# 06_Communication.net
KiCad netlist of a schematic drawn in Altium Designer
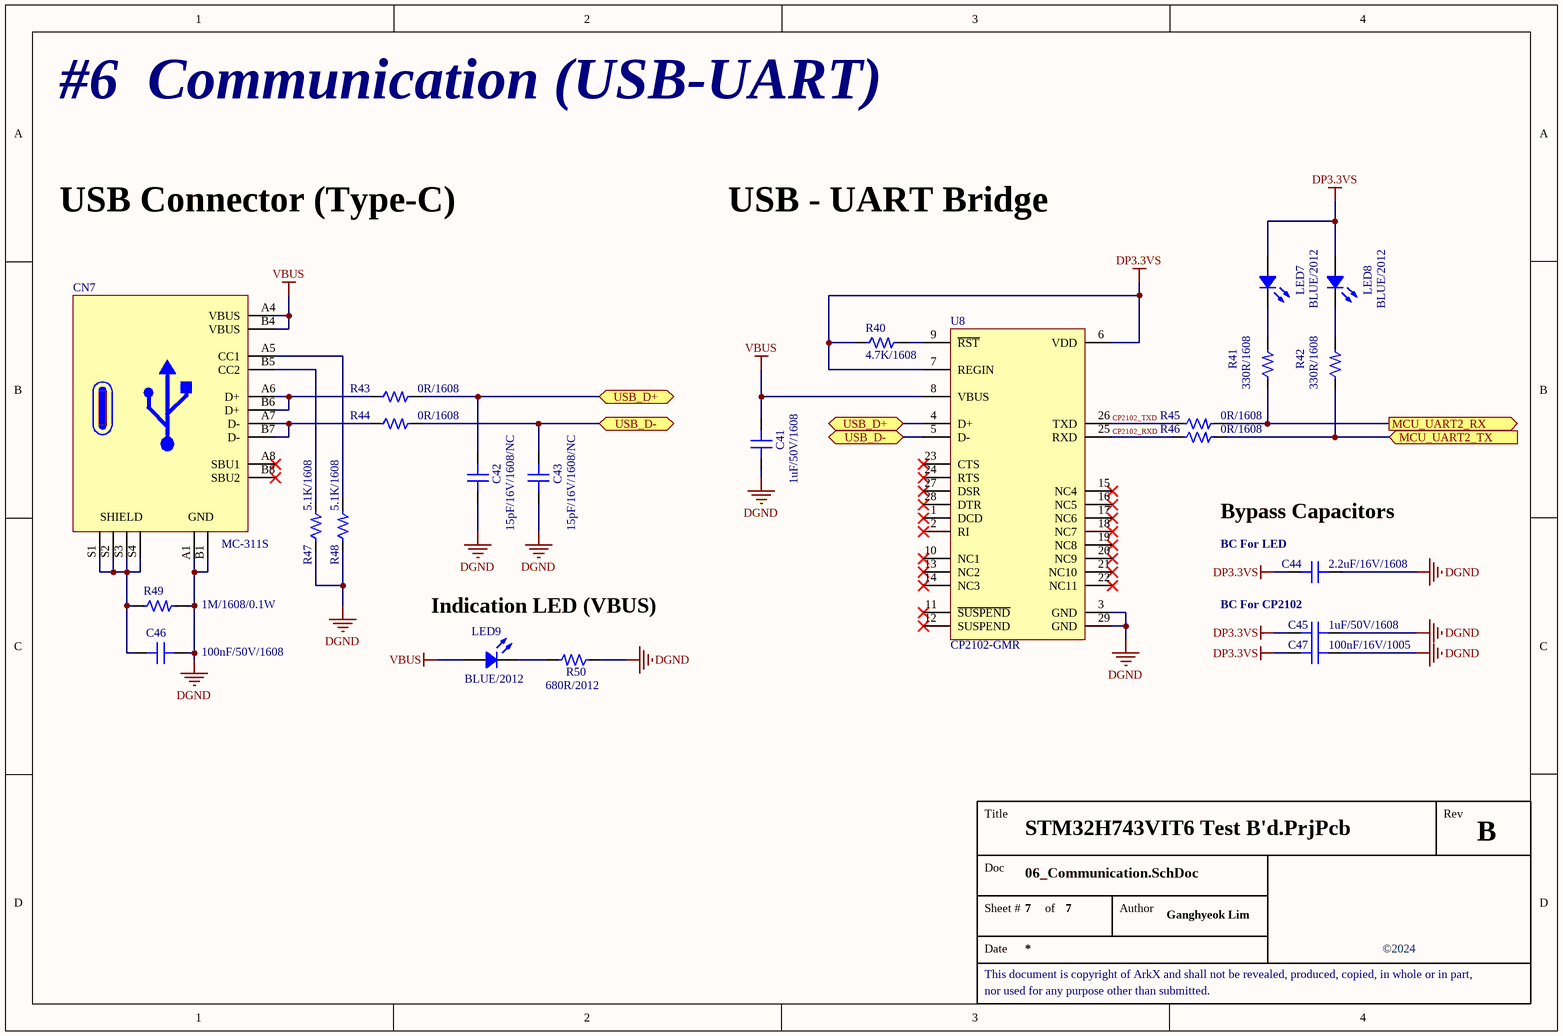
[diagram p0: 06_Communication.SchDoc]

(export (version "E")
  (design (tool "Eeschema 10.0.6"))
  (components
    (comp (ref "C41")
      (value "1uF/50V/1608")
      (footprint "CAP 1608 (0603_INCH)")
      (description "Ceramic CAP_1uF/50V/1608")
      (fields (field (name "LCSC PART #") "C15849"))
      (libsource (lib "Arkx") (part "CAP_1uF/50V/1608"))
    )
    (comp (ref "C42")
      (value "15pF/16V/1608/NC")
      (footprint "CAP 1608 (0603_INCH)/NC")
      (description "Ceramic CAP_15pF/16V/1608")
      (libsource (lib "Arkx") (part "CAP_NC_15pF/16V/1608"))
    )
    (comp (ref "C43")
      (value "15pF/16V/1608/NC")
      (footprint "CAP 1608 (0603_INCH)/NC")
      (description "Ceramic CAP_15pF/16V/1608")
      (libsource (lib "Arkx") (part "CAP_NC_15pF/16V/1608"))
    )
    (comp (ref "C44")
      (value "2.2uF/16V/1608")
      (footprint "CAP 1608 (0603_INCH)")
      (description "Ceramic CAP_2.2uF/16V/1608")
      (fields (field (name "LCSC PART #") "C23630"))
      (libsource (lib "Arkx") (part "CAP_2.2uF/16V/1608"))
    )
    (comp (ref "C45")
      (value "1uF/50V/1608")
      (footprint "CAP 1608 (0603_INCH)")
      (description "Ceramic CAP_1uF/50V/1608")
      (fields (field (name "LCSC PART #") "C15849"))
      (libsource (lib "Arkx") (part "CAP_1uF/50V/1608"))
    )
    (comp (ref "C46")
      (value "100nF/50V/1608")
      (footprint "CAP 1608 (0603_INCH)")
      (description "Ceramic CAP_100nF/50V/1608")
      (fields (field (name "LCSC PART #") "C14663"))
      (libsource (lib "Arkx") (part "CAP_100nF/50V/1608"))
    )
    (comp (ref "C47")
      (value "100nF/16V/1005")
      (footprint "CAP 1005 (0402_INCH)")
      (description "Ceramic CAP_100nF/16V/1005")
      (fields (field (name "LCSC PART #") "C1525"))
      (libsource (lib "Arkx") (part "CAP_100nF/16V/1005"))
    )
    (comp (ref "CN7")
      (value "MC-311S")
      (footprint "CON USB-Type-C (16P)")
      (description "USB 2.0 5A 1 Surface Mount 16 Female -35℃~+75℃ Type-C SMD  USB Connectors ROHS")
      (fields (field (name "LCSC PART #") "C2977718"))
      (libsource (lib "Arkx") (part "CON_USB-Type-C"))
    )
    (comp (ref "LED7")
      (value "BLUE/2012")
      (footprint "LED MHT170RGBCT (BLUE)")
      (fields (field (name "LCSC PART #") "C2962094"))
      (libsource (lib "Arkx") (part "LED_MHT170RGBCT(BLUE)"))
    )
    (comp (ref "LED8")
      (value "BLUE/2012")
      (footprint "LED MHT170RGBCT (BLUE)")
      (fields (field (name "LCSC PART #") "C2962094"))
      (libsource (lib "Arkx") (part "LED_MHT170RGBCT(BLUE)"))
    )
    (comp (ref "LED9")
      (value "BLUE/2012")
      (footprint "LED MHT170RGBCT (BLUE)")
      (fields (field (name "LCSC PART #") "C2962094"))
      (libsource (lib "Arkx") (part "LED_MHT170RGBCT(BLUE)"))
    )
    (comp (ref "R40")
      (value "4.7K/1608")
      (footprint "RES 1608 (0603_inch)")
      (description "RES_4.7K/1608/0.1W")
      (fields (field (name "LCSC PART #") "C23162"))
      (libsource (lib "Arkx") (part "RES_4.7K/1608/0.1W"))
    )
    (comp (ref "R41")
      (value "330R/1608")
      (footprint "RES 1608 (0603_inch)")
      (description "RES_330R/1608/0.1W")
      (fields (field (name "LCSC PART #") "C23138"))
      (libsource (lib "Arkx") (part "RES_330R/1608/0.1W"))
    )
    (comp (ref "R42")
      (value "330R/1608")
      (footprint "RES 1608 (0603_inch)")
      (description "RES_330R/1608/0.1W")
      (fields (field (name "LCSC PART #") "C23138"))
      (libsource (lib "Arkx") (part "RES_330R/1608/0.1W"))
    )
    (comp (ref "R43")
      (value "0R/1608")
      (footprint "RES 1608 (0603_inch)")
      (description "RES_0R/1608/0.1W")
      (fields (field (name "LCSC PART #") "C21189"))
      (libsource (lib "Arkx") (part "RES_0R/1608/0.1W"))
    )
    (comp (ref "R44")
      (value "0R/1608")
      (footprint "RES 1608 (0603_inch)")
      (description "RES_0R/1608/0.1W")
      (fields (field (name "LCSC PART #") "C21189"))
      (libsource (lib "Arkx") (part "RES_0R/1608/0.1W"))
    )
    (comp (ref "R45")
      (value "0R/1608")
      (footprint "RES 1608 (0603_inch)")
      (description "RES_0R/1608/0.1W")
      (fields (field (name "LCSC PART #") "C21189"))
      (libsource (lib "Arkx") (part "RES_0R/1608/0.1W"))
    )
    (comp (ref "R46")
      (value "0R/1608")
      (footprint "RES 1608 (0603_inch)")
      (description "RES_0R/1608/0.1W")
      (fields (field (name "LCSC PART #") "C21189"))
      (libsource (lib "Arkx") (part "RES_0R/1608/0.1W"))
    )
    (comp (ref "R47")
      (value "5.1K/1608")
      (footprint "RES 1608 (0603_inch)")
      (description "RES_5.1K/1608/0.1W")
      (fields (field (name "LCSC PART #") "C23186"))
      (libsource (lib "Arkx") (part "RES_5.1K/1608/0.1W"))
    )
    (comp (ref "R48")
      (value "5.1K/1608")
      (footprint "RES 1608 (0603_inch)")
      (description "RES_5.1K/1608/0.1W")
      (fields (field (name "LCSC PART #") "C23186"))
      (libsource (lib "Arkx") (part "RES_5.1K/1608/0.1W"))
    )
    (comp (ref "R49")
      (value "1M/1608/0.1W")
      (footprint "RES 1608 (0603_inch)")
      (description "RES_1M/1608/0.1W")
      (fields (field (name "LCSC PART #") "C22935"))
      (libsource (lib "Arkx") (part "RES_1M/1608/0.1W"))
    )
    (comp (ref "R50")
      (value "680R/2012")
      (footprint "RES 2012 (0805_inch)")
      (description "RES_680R/2012/0.125W")
      (fields (field (name "LCSC PART #") "C17798"))
      (libsource (lib "Arkx") (part "RES_680R/2012/0.125W"))
    )
    (comp (ref "U8")
      (value "CP2102-GMR")
      (footprint "QFN-28 (5x5mm)")
      (description "Transceiver 1Mbps USB 1/1 QFN-28_5x5x05P  USB ICs ROHS")
      (fields (field (name "LCSC PART #") "C6568"))
      (libsource (lib "Arkx") (part "IC_USB_CP2102"))
    )
  )
  (nets
    (net (code "1") (name "/CP2102_RXD") (class "Default")
      (node (ref "R46") (pin "1") (pinfunction "1_1") (pintype "passive"))
      (node (ref "U8") (pin "25") (pinfunction "RXD_25") (pintype "passive"))
    )
    (net (code "2") (name "/CP2102_TXD") (class "Default")
      (node (ref "R45") (pin "1") (pinfunction "1_1") (pintype "passive"))
      (node (ref "U8") (pin "26") (pinfunction "TXD_26") (pintype "passive"))
    )
    (net (code "3") (name "/MCU_UART2_RX") (class "Default")
      (node (ref "R41") (pin "1") (pinfunction "1_1") (pintype "passive"))
      (node (ref "R45") (pin "2") (pinfunction "2_2") (pintype "passive"))
    )
    (net (code "4") (name "/MCU_UART2_TX") (class "Default")
      (node (ref "R42") (pin "1") (pinfunction "1_1") (pintype "passive"))
      (node (ref "R46") (pin "2") (pinfunction "2_2") (pintype "passive"))
    )
    (net (code "5") (name "/USB_D+") (class "Default")
      (node (ref "C42") (pin "2") (pinfunction "2_2") (pintype "passive"))
      (node (ref "R43") (pin "2") (pinfunction "2_2") (pintype "passive"))
      (node (ref "U8") (pin "4") (pinfunction "D+_4") (pintype "passive"))
    )
    (net (code "6") (name "/USB_D-") (class "Default")
      (node (ref "C43") (pin "2") (pinfunction "2_2") (pintype "passive"))
      (node (ref "R44") (pin "2") (pinfunction "2_2") (pintype "passive"))
      (node (ref "U8") (pin "5") (pinfunction "D-_5") (pintype "passive"))
    )
    (net (code "7") (name "DGND") (class "Default")
      (node (ref "C41") (pin "1") (pinfunction "1_1") (pintype "passive"))
      (node (ref "C42") (pin "1") (pinfunction "1_1") (pintype "passive"))
      (node (ref "C43") (pin "1") (pinfunction "1_1") (pintype "passive"))
      (node (ref "C44") (pin "2") (pinfunction "2_2") (pintype "passive"))
      (node (ref "C45") (pin "1") (pinfunction "1_1") (pintype "passive"))
      (node (ref "C46") (pin "2") (pinfunction "2_2") (pintype "passive"))
      (node (ref "C47") (pin "1") (pinfunction "1_1") (pintype "passive"))
      (node (ref "CN7") (pin "A1") (pinfunction "GND_A1") (pintype "passive"))
      (node (ref "CN7") (pin "B1") (pinfunction "GND_B1") (pintype "passive"))
      (node (ref "R47") (pin "1") (pinfunction "1_1") (pintype "passive"))
      (node (ref "R48") (pin "1") (pinfunction "1_1") (pintype "passive"))
      (node (ref "R49") (pin "2") (pinfunction "2_2") (pintype "passive"))
      (node (ref "R50") (pin "1") (pinfunction "1_1") (pintype "passive"))
      (node (ref "U8") (pin "29") (pinfunction "GND_29") (pintype "passive"))
      (node (ref "U8") (pin "3") (pinfunction "GND_3") (pintype "passive"))
    )
    (net (code "8") (name "DP3.3VS") (class "Default")
      (node (ref "C44") (pin "1") (pinfunction "1_1") (pintype "passive"))
      (node (ref "C45") (pin "2") (pinfunction "2_2") (pintype "passive"))
      (node (ref "C47") (pin "2") (pinfunction "2_2") (pintype "passive"))
      (node (ref "LED7") (pin "4") (pinfunction "Common_Anode_4") (pintype "passive"))
      (node (ref "LED8") (pin "4") (pinfunction "Common_Anode_4") (pintype "passive"))
      (node (ref "R40") (pin "1") (pinfunction "1_1") (pintype "passive"))
      (node (ref "U8") (pin "6") (pinfunction "VDD_6") (pintype "passive"))
      (node (ref "U8") (pin "7") (pinfunction "REGIN_7") (pintype "passive"))
    )
    (net (code "9") (name "Net-(C46-Pad1)") (class "Default")
      (node (ref "C46") (pin "1") (pinfunction "1_1") (pintype "passive"))
      (node (ref "CN7") (pin "S1") (pinfunction "SHIELD_S1") (pintype "passive"))
      (node (ref "CN7") (pin "S2") (pinfunction "SHIELD_S2") (pintype "passive"))
      (node (ref "CN7") (pin "S3") (pinfunction "SHIELD_S3") (pintype "passive"))
      (node (ref "CN7") (pin "S4") (pinfunction "SHIELD_S4") (pintype "passive"))
      (node (ref "R49") (pin "1") (pinfunction "1_1") (pintype "passive"))
    )
    (net (code "10") (name "Net-(CN7-CC1)") (class "Default")
      (node (ref "CN7") (pin "A5") (pinfunction "CC1_A5") (pintype "passive"))
      (node (ref "R48") (pin "2") (pinfunction "2_2") (pintype "passive"))
    )
    (net (code "11") (name "Net-(CN7-CC2)") (class "Default")
      (node (ref "CN7") (pin "B5") (pinfunction "CC2_B5") (pintype "passive"))
      (node (ref "R47") (pin "2") (pinfunction "2_2") (pintype "passive"))
    )
    (net (code "12") (name "Net-(CN7-D+-PadA6)") (class "Default")
      (node (ref "CN7") (pin "A6") (pinfunction "D+_A6") (pintype "passive"))
      (node (ref "CN7") (pin "B6") (pinfunction "D+_B6") (pintype "passive"))
      (node (ref "R43") (pin "1") (pinfunction "1_1") (pintype "passive"))
    )
    (net (code "13") (name "Net-(CN7-D--PadA7)") (class "Default")
      (node (ref "CN7") (pin "A7") (pinfunction "D-_A7") (pintype "passive"))
      (node (ref "CN7") (pin "B7") (pinfunction "D-_B7") (pintype "passive"))
      (node (ref "R44") (pin "1") (pinfunction "1_1") (pintype "passive"))
    )
    (net (code "14") (name "Net-(LED7-BLUE)") (class "Default")
      (node (ref "LED7") (pin "3") (pinfunction "BLUE_3") (pintype "passive"))
      (node (ref "R41") (pin "2") (pinfunction "2_2") (pintype "passive"))
    )
    (net (code "15") (name "Net-(LED8-BLUE)") (class "Default")
      (node (ref "LED8") (pin "3") (pinfunction "BLUE_3") (pintype "passive"))
      (node (ref "R42") (pin "2") (pinfunction "2_2") (pintype "passive"))
    )
    (net (code "16") (name "Net-(LED9-BLUE)") (class "Default")
      (node (ref "LED9") (pin "3") (pinfunction "BLUE_3") (pintype "passive"))
      (node (ref "R50") (pin "2") (pinfunction "2_2") (pintype "passive"))
    )
    (net (code "17") (name "Net-(U8-~{RST})") (class "Default")
      (node (ref "R40") (pin "2") (pinfunction "2_2") (pintype "passive"))
      (node (ref "U8") (pin "9") (pinfunction "~{RST}_9") (pintype "passive"))
    )
    (net (code "18") (name "VBUS") (class "Default")
      (node (ref "C41") (pin "2") (pinfunction "2_2") (pintype "passive"))
      (node (ref "CN7") (pin "A4") (pinfunction "VBUS_A4") (pintype "passive"))
      (node (ref "CN7") (pin "B4") (pinfunction "VBUS_B4") (pintype "passive"))
      (node (ref "LED9") (pin "4") (pinfunction "Common_Anode_4") (pintype "passive"))
      (node (ref "U8") (pin "8") (pinfunction "VBUS_8") (pintype "passive"))
    )
    (net (code "19") (name "unconnected-(CN7-SBU1-PadA8)") (class "Default")
      (node (ref "CN7") (pin "A8") (pinfunction "SBU1_A8") (pintype "passive+no_connect"))
    )
    (net (code "20") (name "unconnected-(CN7-SBU2-PadB8)") (class "Default")
      (node (ref "CN7") (pin "B8") (pinfunction "SBU2_B8") (pintype "passive+no_connect"))
    )
    (net (code "21") (name "unconnected-(U8-CTS-Pad23)") (class "Default")
      (node (ref "U8") (pin "23") (pinfunction "CTS_23") (pintype "passive+no_connect"))
    )
    (net (code "22") (name "unconnected-(U8-DCD-Pad1)") (class "Default")
      (node (ref "U8") (pin "1") (pinfunction "DCD_1") (pintype "passive+no_connect"))
    )
    (net (code "23") (name "unconnected-(U8-DSR-Pad27)") (class "Default")
      (node (ref "U8") (pin "27") (pinfunction "DSR_27") (pintype "passive+no_connect"))
    )
    (net (code "24") (name "unconnected-(U8-DTR-Pad28)") (class "Default")
      (node (ref "U8") (pin "28") (pinfunction "DTR_28") (pintype "passive+no_connect"))
    )
    (net (code "25") (name "unconnected-(U8-NC1-Pad10)") (class "Default")
      (node (ref "U8") (pin "10") (pinfunction "NC1_10") (pintype "passive+no_connect"))
    )
    (net (code "26") (name "unconnected-(U8-NC2-Pad13)") (class "Default")
      (node (ref "U8") (pin "13") (pinfunction "NC2_13") (pintype "passive+no_connect"))
    )
    (net (code "27") (name "unconnected-(U8-NC3-Pad14)") (class "Default")
      (node (ref "U8") (pin "14") (pinfunction "NC3_14") (pintype "passive+no_connect"))
    )
    (net (code "28") (name "unconnected-(U8-NC4-Pad15)") (class "Default")
      (node (ref "U8") (pin "15") (pinfunction "NC4_15") (pintype "passive+no_connect"))
    )
    (net (code "29") (name "unconnected-(U8-NC5-Pad16)") (class "Default")
      (node (ref "U8") (pin "16") (pinfunction "NC5_16") (pintype "passive+no_connect"))
    )
    (net (code "30") (name "unconnected-(U8-NC6-Pad17)") (class "Default")
      (node (ref "U8") (pin "17") (pinfunction "NC6_17") (pintype "passive+no_connect"))
    )
    (net (code "31") (name "unconnected-(U8-NC7-Pad18)") (class "Default")
      (node (ref "U8") (pin "18") (pinfunction "NC7_18") (pintype "passive+no_connect"))
    )
    (net (code "32") (name "unconnected-(U8-NC8-Pad19)") (class "Default")
      (node (ref "U8") (pin "19") (pinfunction "NC8_19") (pintype "passive+no_connect"))
    )
    (net (code "33") (name "unconnected-(U8-NC9-Pad20)") (class "Default")
      (node (ref "U8") (pin "20") (pinfunction "NC9_20") (pintype "passive+no_connect"))
    )
    (net (code "34") (name "unconnected-(U8-NC10-Pad21)") (class "Default")
      (node (ref "U8") (pin "21") (pinfunction "NC10_21") (pintype "passive+no_connect"))
    )
    (net (code "35") (name "unconnected-(U8-NC11-Pad22)") (class "Default")
      (node (ref "U8") (pin "22") (pinfunction "NC11_22") (pintype "passive+no_connect"))
    )
    (net (code "36") (name "unconnected-(U8-RI-Pad2)") (class "Default")
      (node (ref "U8") (pin "2") (pinfunction "RI_2") (pintype "passive+no_connect"))
    )
    (net (code "37") (name "unconnected-(U8-RTS-Pad24)") (class "Default")
      (node (ref "U8") (pin "24") (pinfunction "RTS_24") (pintype "passive+no_connect"))
    )
    (net (code "38") (name "unconnected-(U8-SUSPEND-Pad12)") (class "Default")
      (node (ref "U8") (pin "12") (pinfunction "SUSPEND_12") (pintype "passive+no_connect"))
    )
    (net (code "39") (name "unconnected-(U8-~{SUSPEND}-Pad11)") (class "Default")
      (node (ref "U8") (pin "11") (pinfunction "~{SUSPEND}_11") (pintype "passive+no_connect"))
    )
  )
)
